# esp8266_room_monitor.net
KiCad netlist of a schematic drawn in EAGLE
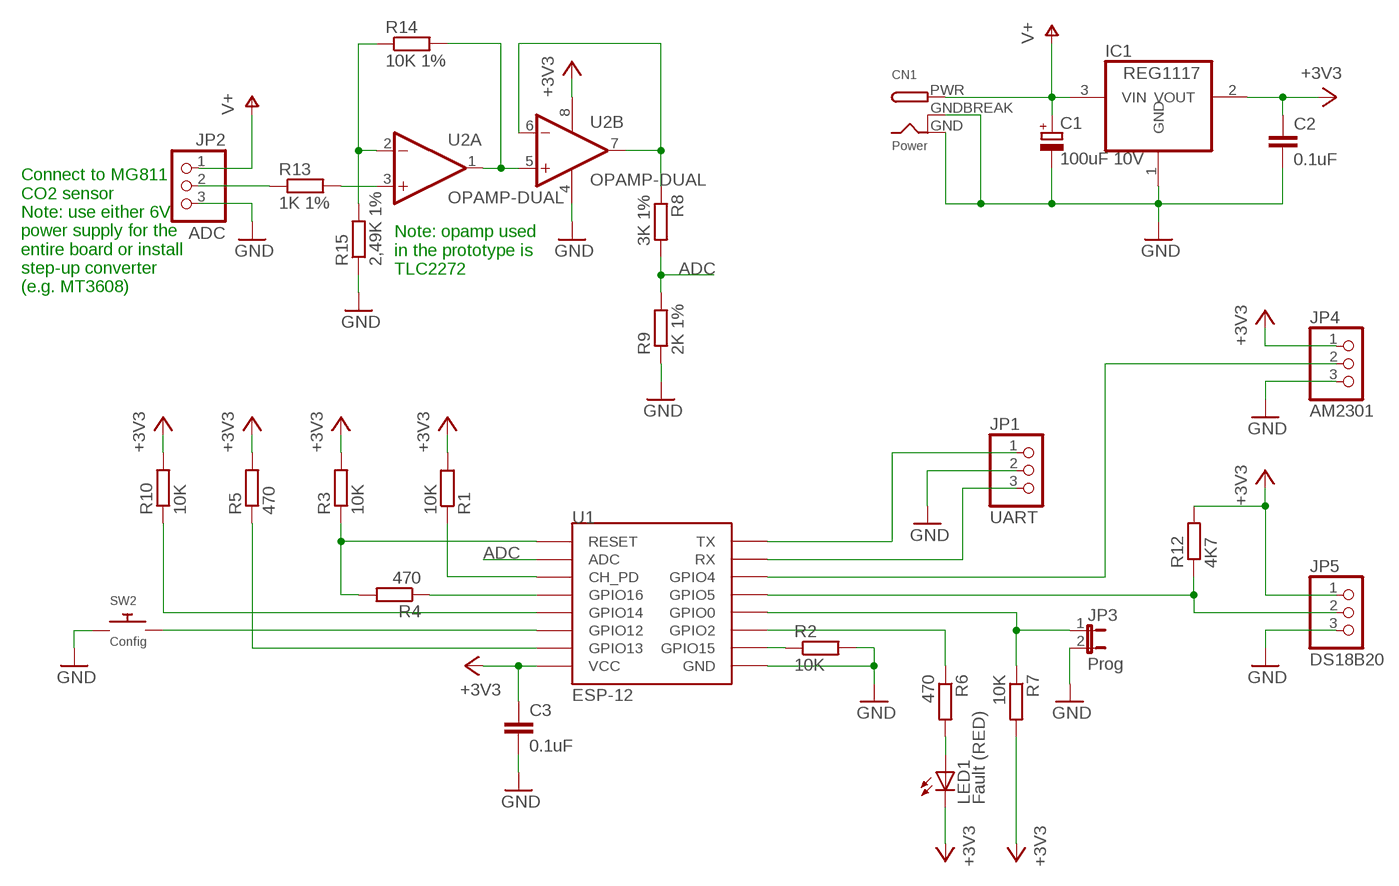
[diagram p0: schematic, sheet 1]

(export (version "E")
  (design (tool "Eeschema 10.0.6"))
  (components
    (comp (ref "C1")
      (value "100uF 10V")
      (footprint "eagle-import:E_7260-38W")
      (libsource (lib "eagle-import") (part "CPOL-EUE/7260-38W"))
    )
    (comp (ref "C2")
      (value "0.1uF")
      (footprint "eagle-import:C0805")
      (libsource (lib "eagle-import") (part "C-EUC0805"))
    )
    (comp (ref "C3")
      (value "0.1uF")
      (footprint "eagle-import:C0805")
      (libsource (lib "eagle-import") (part "C-EUC0805"))
    )
    (comp (ref "CN1")
      (value "Power")
      (footprint "eagle-import:DCJACK_2MM_PTH")
      (libsource (lib "eagle-import") (part "DCBARRELPTH"))
    )
    (comp (ref "IC1")
      (value "REG1117")
      (footprint "eagle-import:SOT223")
      (libsource (lib "eagle-import") (part "REG1117"))
    )
    (comp (ref "JP1")
      (value "UART")
      (footprint "eagle-import:1X03")
      (libsource (lib "eagle-import") (part "PINHD-1X3"))
    )
    (comp (ref "JP2")
      (value "ADC")
      (footprint "eagle-import:1X03")
      (libsource (lib "eagle-import") (part "PINHD-1X3"))
    )
    (comp (ref "JP3")
      (value "Prog")
      (footprint "eagle-import:JP1")
      (libsource (lib "eagle-import") (part "JP1E"))
    )
    (comp (ref "JP4")
      (value "AM2301")
      (footprint "eagle-import:1X03")
      (libsource (lib "eagle-import") (part "PINHD-1X3"))
    )
    (comp (ref "JP5")
      (value "DS18B20")
      (footprint "eagle-import:1X03")
      (libsource (lib "eagle-import") (part "PINHD-1X3"))
    )
    (comp (ref "LED1")
      (value "Fault (RED)")
      (footprint "eagle-import:LED5MM")
      (libsource (lib "eagle-import") (part "LED5MM"))
    )
    (comp (ref "R1")
      (value "10K")
      (footprint "eagle-import:R0805")
      (libsource (lib "eagle-import") (part "R-EU_R0805"))
    )
    (comp (ref "R2")
      (value "10K")
      (footprint "eagle-import:R0805")
      (libsource (lib "eagle-import") (part "R-EU_R0805"))
    )
    (comp (ref "R3")
      (value "10K")
      (footprint "eagle-import:M0805")
      (libsource (lib "eagle-import") (part "R-EU_M0805"))
    )
    (comp (ref "R4")
      (value "470")
      (footprint "eagle-import:M0805")
      (libsource (lib "eagle-import") (part "R-EU_M0805"))
    )
    (comp (ref "R5")
      (value "470")
      (footprint "eagle-import:M0805")
      (libsource (lib "eagle-import") (part "R-EU_M0805"))
    )
    (comp (ref "R6")
      (value "470")
      (footprint "eagle-import:M0805")
      (libsource (lib "eagle-import") (part "R-EU_M0805"))
    )
    (comp (ref "R7")
      (value "10K")
      (footprint "eagle-import:M0805")
      (libsource (lib "eagle-import") (part "R-EU_M0805"))
    )
    (comp (ref "R8")
      (value "3K 1%")
      (footprint "eagle-import:M0805")
      (libsource (lib "eagle-import") (part "R-EU_M0805"))
    )
    (comp (ref "R9")
      (value "2K 1%")
      (footprint "eagle-import:M0805")
      (libsource (lib "eagle-import") (part "R-EU_M0805"))
    )
    (comp (ref "R10")
      (value "10K")
      (footprint "eagle-import:M0805")
      (libsource (lib "eagle-import") (part "R-EU_M0805"))
    )
    (comp (ref "R12")
      (value "4K7")
      (footprint "eagle-import:M0805")
      (libsource (lib "eagle-import") (part "R-EU_M0805"))
    )
    (comp (ref "R13")
      (value "1K 1%")
      (footprint "eagle-import:M0805")
      (libsource (lib "eagle-import") (part "R-EU_M0805"))
    )
    (comp (ref "R14")
      (value "10K 1%")
      (footprint "eagle-import:M0805")
      (libsource (lib "eagle-import") (part "R-EU_M0805"))
    )
    (comp (ref "R15")
      (value "2,49K 1%")
      (footprint "eagle-import:M0805")
      (libsource (lib "eagle-import") (part "R-EU_M0805"))
    )
    (comp (ref "SW2")
      (value "Config")
      (footprint "eagle-import:BTN_CK_KSS")
      (libsource (lib "eagle-import") (part "SWITCH_PUSHBUTTONC&K_KSS"))
    )
    (comp (ref "U1")
      (value "ESP-12")
      (footprint "eagle-import:ESP12-SMD")
      (libsource (lib "eagle-import") (part "ESP12SMD"))
    )
    (comp (ref "U2")
      (value "OPAMP-DUAL")
      (footprint "eagle-import:DIP8")
      (libsource (lib "eagle-import") (part "OPAMP-DUAL"))
    )
  )
  (nets
    (net (code "1") (name "+3V3") (class "Default")
      (node (ref "C2") (pin "1") (pinfunction "1_1") (pintype "passive"))
      (node (ref "C3") (pin "1") (pinfunction "1_1") (pintype "passive"))
      (node (ref "IC1") (pin "2") (pinfunction "VOUT_2") (pintype "power_in"))
      (node (ref "JP4") (pin "1") (pinfunction "1_1") (pintype "passive"))
      (node (ref "JP5") (pin "1") (pinfunction "1_1") (pintype "passive"))
      (node (ref "LED1") (pin "K") (pinfunction "C_K") (pintype "passive"))
      (node (ref "R1") (pin "2") (pinfunction "2_2") (pintype "passive"))
      (node (ref "R10") (pin "2") (pinfunction "2_2") (pintype "passive"))
      (node (ref "R12") (pin "2") (pinfunction "2_2") (pintype "passive"))
      (node (ref "R3") (pin "2") (pinfunction "2_2") (pintype "passive"))
      (node (ref "R5") (pin "2") (pinfunction "2_2") (pintype "passive"))
      (node (ref "R7") (pin "2") (pinfunction "2_2") (pintype "passive"))
      (node (ref "U1") (pin "VCC") (pinfunction "VCC_VCC") (pintype "bidirectional"))
      (node (ref "U2") (pin "8") (pinfunction "VCC_8") (pintype "power_in"))
    )
    (net (code "2") (name "/ADC") (class "Default")
      (node (ref "R8") (pin "2") (pinfunction "2_2") (pintype "passive"))
      (node (ref "R9") (pin "2") (pinfunction "2_2") (pintype "passive"))
      (node (ref "U1") (pin "ADC") (pinfunction "ADC_ADC") (pintype "bidirectional"))
    )
    (net (code "3") (name "GND") (class "Default")
      (node (ref "C1") (pin "-") (pinfunction "-_-") (pintype "passive"))
      (node (ref "C2") (pin "2") (pinfunction "2_2") (pintype "passive"))
      (node (ref "C3") (pin "2") (pinfunction "2_2") (pintype "passive"))
      (node (ref "CN1") (pin "GND") (pinfunction "GND_GND") (pintype "power_in"))
      (node (ref "CN1") (pin "GNDBREAK") (pinfunction "GNDBREAK_GNDBREAK") (pintype "power_in"))
      (node (ref "IC1") (pin "1") (pinfunction "GND_1") (pintype "power_in"))
      (node (ref "JP1") (pin "2") (pinfunction "2_2") (pintype "passive"))
      (node (ref "JP2") (pin "3") (pinfunction "3_3") (pintype "passive"))
      (node (ref "JP3") (pin "2") (pinfunction "2_2") (pintype "passive"))
      (node (ref "JP4") (pin "3") (pinfunction "3_3") (pintype "passive"))
      (node (ref "JP5") (pin "3") (pinfunction "3_3") (pintype "passive"))
      (node (ref "R15") (pin "1") (pinfunction "1_1") (pintype "passive"))
      (node (ref "R2") (pin "2") (pinfunction "2_2") (pintype "passive"))
      (node (ref "R9") (pin "1") (pinfunction "1_1") (pintype "passive"))
      (node (ref "SW2") (pin "P$1") (pinfunction "P$1_P$1") (pintype "passive"))
      (node (ref "U1") (pin "GND") (pinfunction "GND_GND") (pintype "bidirectional"))
      (node (ref "U2") (pin "4") (pinfunction "VEE_4") (pintype "power_in"))
    )
    (net (code "4") (name "Net-(JP2-Pad2)") (class "Default")
      (node (ref "JP2") (pin "2") (pinfunction "2_2") (pintype "passive"))
      (node (ref "R13") (pin "1") (pinfunction "1_1") (pintype "passive"))
    )
    (net (code "5") (name "Net-(JP3-Pad1)") (class "Default")
      (node (ref "JP3") (pin "1") (pinfunction "1_1") (pintype "passive"))
      (node (ref "R7") (pin "1") (pinfunction "1_1") (pintype "passive"))
      (node (ref "U1") (pin "GPIO0") (pinfunction "GPIO0_GPIO0") (pintype "bidirectional"))
    )
    (net (code "6") (name "Net-(JP4-Pad2)") (class "Default")
      (node (ref "JP4") (pin "2") (pinfunction "2_2") (pintype "passive"))
      (node (ref "U1") (pin "GPIO4") (pinfunction "GPIO4_GPIO4") (pintype "bidirectional"))
    )
    (net (code "7") (name "Net-(JP5-Pad2)") (class "Default")
      (node (ref "JP5") (pin "2") (pinfunction "2_2") (pintype "passive"))
      (node (ref "R12") (pin "1") (pinfunction "1_1") (pintype "passive"))
      (node (ref "U1") (pin "GPIO5") (pinfunction "GPIO5_GPIO5") (pintype "bidirectional"))
    )
    (net (code "8") (name "Net-(LED1-PadA)") (class "Default")
      (node (ref "LED1") (pin "A") (pinfunction "A_A") (pintype "passive"))
      (node (ref "R6") (pin "2") (pinfunction "2_2") (pintype "passive"))
    )
    (net (code "9") (name "Net-(R1-Pad1)") (class "Default")
      (node (ref "R1") (pin "1") (pinfunction "1_1") (pintype "passive"))
      (node (ref "U1") (pin "CH_PD") (pinfunction "CH_PD_CH_PD") (pintype "bidirectional"))
    )
    (net (code "10") (name "Net-(R2-Pad1)") (class "Default")
      (node (ref "R2") (pin "1") (pinfunction "1_1") (pintype "passive"))
      (node (ref "U1") (pin "GPIO15") (pinfunction "GPIO15_GPIO15") (pintype "bidirectional"))
    )
    (net (code "11") (name "Net-(R3-Pad1)") (class "Default")
      (node (ref "R3") (pin "1") (pinfunction "1_1") (pintype "passive"))
      (node (ref "R4") (pin "2") (pinfunction "2_2") (pintype "passive"))
      (node (ref "U1") (pin "RESET") (pinfunction "RESET_RESET") (pintype "bidirectional"))
    )
    (net (code "12") (name "Net-(R4-Pad1)") (class "Default")
      (node (ref "R4") (pin "1") (pinfunction "1_1") (pintype "passive"))
      (node (ref "U1") (pin "GPIO16") (pinfunction "GPIO16_GPIO16") (pintype "bidirectional"))
    )
    (net (code "13") (name "Net-(R5-Pad1)") (class "Default")
      (node (ref "R5") (pin "1") (pinfunction "1_1") (pintype "passive"))
      (node (ref "U1") (pin "GPIO13") (pinfunction "GPIO13_GPIO13") (pintype "bidirectional"))
    )
    (net (code "14") (name "Net-(R6-Pad1)") (class "Default")
      (node (ref "R6") (pin "1") (pinfunction "1_1") (pintype "passive"))
      (node (ref "U1") (pin "GPIO2") (pinfunction "GPIO2_GPIO2") (pintype "bidirectional"))
    )
    (net (code "15") (name "Net-(R10-Pad1)") (class "Default")
      (node (ref "R10") (pin "1") (pinfunction "1_1") (pintype "passive"))
      (node (ref "U1") (pin "GPIO14") (pinfunction "GPIO14_GPIO14") (pintype "bidirectional"))
    )
    (net (code "16") (name "Net-(SW2-PadP$2)") (class "Default")
      (node (ref "SW2") (pin "P$2") (pinfunction "P$2_P$2") (pintype "passive"))
      (node (ref "U1") (pin "GPIO12") (pinfunction "GPIO12_GPIO12") (pintype "bidirectional"))
    )
    (net (code "17") (name "Net-(U1-RX)") (class "Default")
      (node (ref "JP1") (pin "3") (pinfunction "3_3") (pintype "passive"))
      (node (ref "U1") (pin "RXD0") (pinfunction "RX_RXD0") (pintype "bidirectional"))
    )
    (net (code "18") (name "Net-(U1-TX)") (class "Default")
      (node (ref "JP1") (pin "1") (pinfunction "1_1") (pintype "passive"))
      (node (ref "U1") (pin "TXD0") (pinfunction "TX_TXD0") (pintype "bidirectional"))
    )
    (net (code "19") (name "Net-(U2A-IN+)") (class "Default")
      (node (ref "R13") (pin "2") (pinfunction "2_2") (pintype "passive"))
      (node (ref "U2") (pin "3") (pinfunction "IN+_3") (pintype "input"))
    )
    (net (code "20") (name "Net-(U2A-IN-)") (class "Default")
      (node (ref "R14") (pin "1") (pinfunction "1_1") (pintype "passive"))
      (node (ref "R15") (pin "2") (pinfunction "2_2") (pintype "passive"))
      (node (ref "U2") (pin "2") (pinfunction "IN-_2") (pintype "input"))
    )
    (net (code "21") (name "Net-(U2A-OUT)") (class "Default")
      (node (ref "R14") (pin "2") (pinfunction "2_2") (pintype "passive"))
      (node (ref "U2") (pin "1") (pinfunction "OUT_1") (pintype "output"))
      (node (ref "U2") (pin "5") (pinfunction "IN+_5") (pintype "input"))
    )
    (net (code "22") (name "Net-(U2B-IN-)") (class "Default")
      (node (ref "R8") (pin "1") (pinfunction "1_1") (pintype "passive"))
      (node (ref "U2") (pin "6") (pinfunction "IN-_6") (pintype "input"))
      (node (ref "U2") (pin "7") (pinfunction "OUT_7") (pintype "output"))
    )
    (net (code "23") (name "V+") (class "Default")
      (node (ref "C1") (pin "+") (pinfunction "+_+") (pintype "passive"))
      (node (ref "CN1") (pin "PWR") (pinfunction "PWR_PWR") (pintype "power_in"))
      (node (ref "IC1") (pin "3") (pinfunction "VIN_3") (pintype "input"))
      (node (ref "JP2") (pin "1") (pinfunction "1_1") (pintype "passive"))
    )
  )
)
